# 4_ADC_DECOUPLING.net
KiCad netlist of a schematic drawn in Altium Designer
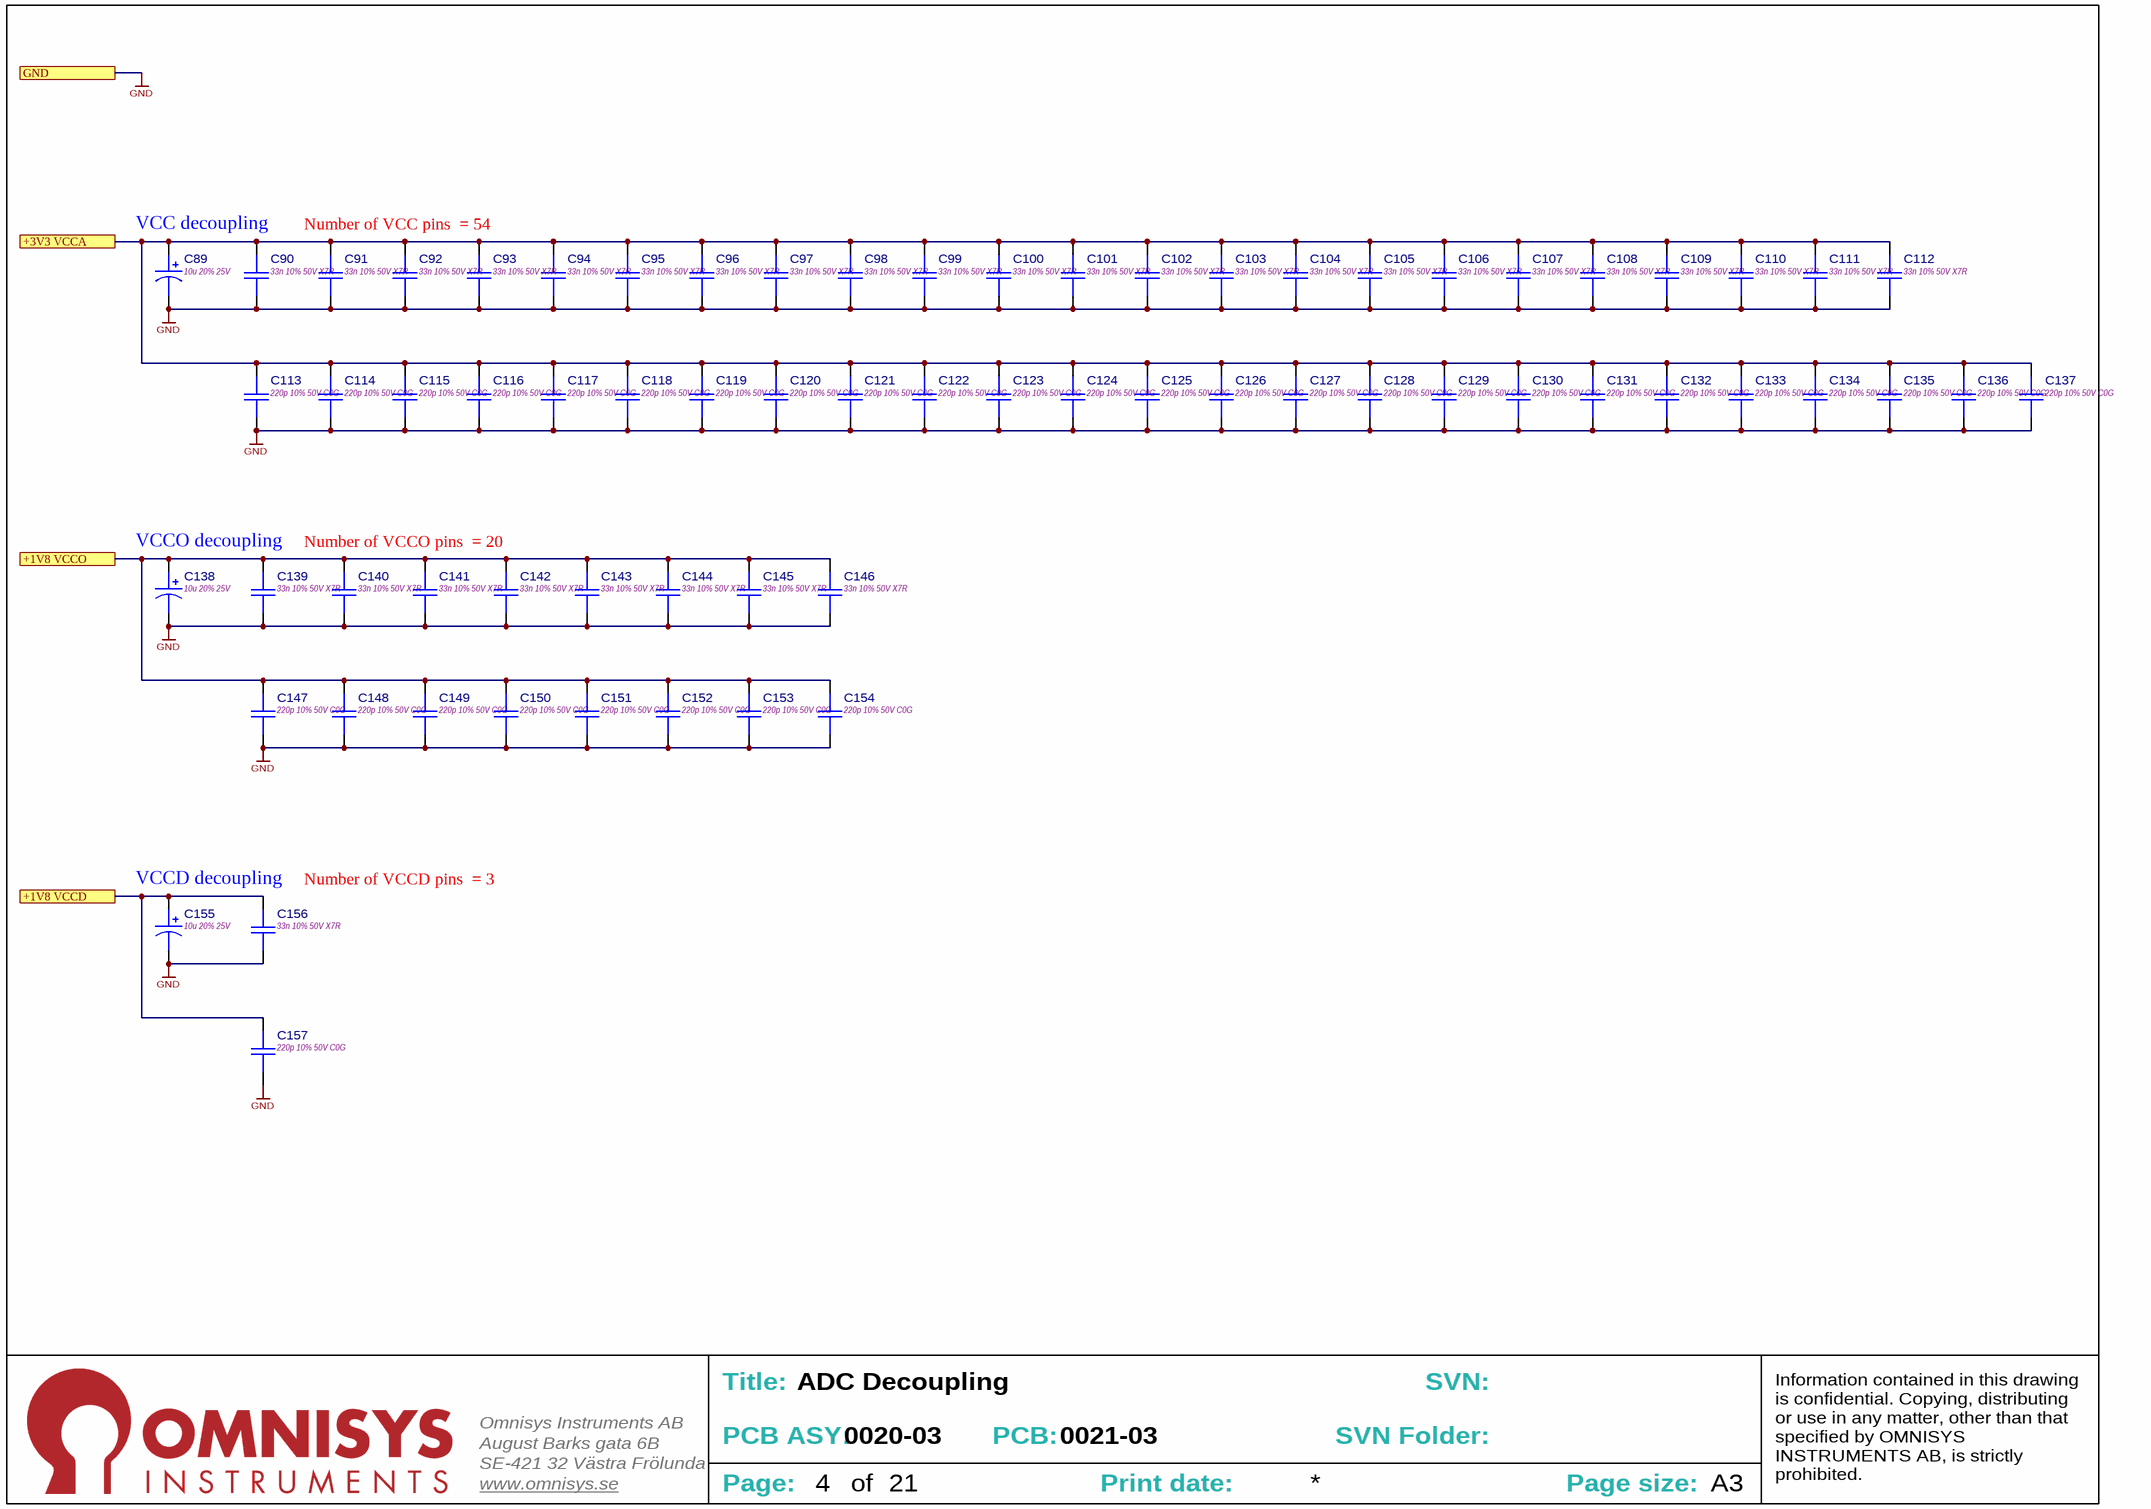
[diagram p0: [4] ADC_DECOUPLING.SchDoc]

(export (version "E")
  (design (tool "Eeschema 10.0.6"))
  (components
    (comp (ref "C89")
      (value "10u 20% 25V")
      (footprint "CAPMP3528X21N")
      (description "Standard tantalum capacitor, 3528/Case B")
      (fields (field (name "TOLERANCE") "20%"))
      (libsource (lib "Omnisys Vault") (part "CAP-2PIN-POL"))
    )
    (comp (ref "C90")
      (value "33n 10% 50V X7R")
      (footprint "CAPC1005X55L")
      (description "Ceramic Chip Capacitor, 0402/1005")
      (fields (field (name "TOLERANCE") "10%"))
      (libsource (lib "Omnisys Vault") (part "CAP-2PIN"))
    )
    (comp (ref "C91")
      (value "33n 10% 50V X7R")
      (footprint "CAPC1005X55L")
      (description "Ceramic Chip Capacitor, 0402/1005")
      (fields (field (name "TOLERANCE") "10%"))
      (libsource (lib "Omnisys Vault") (part "CAP-2PIN"))
    )
    (comp (ref "C92")
      (value "33n 10% 50V X7R")
      (footprint "CAPC1005X55L")
      (description "Ceramic Chip Capacitor, 0402/1005")
      (fields (field (name "TOLERANCE") "10%"))
      (libsource (lib "Omnisys Vault") (part "CAP-2PIN"))
    )
    (comp (ref "C93")
      (value "33n 10% 50V X7R")
      (footprint "CAPC1005X55L")
      (description "Ceramic Chip Capacitor, 0402/1005")
      (fields (field (name "TOLERANCE") "10%"))
      (libsource (lib "Omnisys Vault") (part "CAP-2PIN"))
    )
    (comp (ref "C94")
      (value "33n 10% 50V X7R")
      (footprint "CAPC1005X55L")
      (description "Ceramic Chip Capacitor, 0402/1005")
      (fields (field (name "TOLERANCE") "10%"))
      (libsource (lib "Omnisys Vault") (part "CAP-2PIN"))
    )
    (comp (ref "C95")
      (value "33n 10% 50V X7R")
      (footprint "CAPC1005X55L")
      (description "Ceramic Chip Capacitor, 0402/1005")
      (fields (field (name "TOLERANCE") "10%"))
      (libsource (lib "Omnisys Vault") (part "CAP-2PIN"))
    )
    (comp (ref "C96")
      (value "33n 10% 50V X7R")
      (footprint "CAPC1005X55L")
      (description "Ceramic Chip Capacitor, 0402/1005")
      (fields (field (name "TOLERANCE") "10%"))
      (libsource (lib "Omnisys Vault") (part "CAP-2PIN"))
    )
    (comp (ref "C97")
      (value "33n 10% 50V X7R")
      (footprint "CAPC1005X55L")
      (description "Ceramic Chip Capacitor, 0402/1005")
      (fields (field (name "TOLERANCE") "10%"))
      (libsource (lib "Omnisys Vault") (part "CAP-2PIN"))
    )
    (comp (ref "C98")
      (value "33n 10% 50V X7R")
      (footprint "CAPC1005X55L")
      (description "Ceramic Chip Capacitor, 0402/1005")
      (fields (field (name "TOLERANCE") "10%"))
      (libsource (lib "Omnisys Vault") (part "CAP-2PIN"))
    )
    (comp (ref "C99")
      (value "33n 10% 50V X7R")
      (footprint "CAPC1005X55L")
      (description "Ceramic Chip Capacitor, 0402/1005")
      (fields (field (name "TOLERANCE") "10%"))
      (libsource (lib "Omnisys Vault") (part "CAP-2PIN"))
    )
    (comp (ref "C100")
      (value "33n 10% 50V X7R")
      (footprint "CAPC1005X55L")
      (description "Ceramic Chip Capacitor, 0402/1005")
      (fields (field (name "TOLERANCE") "10%"))
      (libsource (lib "Omnisys Vault") (part "CAP-2PIN"))
    )
    (comp (ref "C101")
      (value "33n 10% 50V X7R")
      (footprint "CAPC1005X55L")
      (description "Ceramic Chip Capacitor, 0402/1005")
      (fields (field (name "TOLERANCE") "10%"))
      (libsource (lib "Omnisys Vault") (part "CAP-2PIN"))
    )
    (comp (ref "C102")
      (value "33n 10% 50V X7R")
      (footprint "CAPC1005X55L")
      (description "Ceramic Chip Capacitor, 0402/1005")
      (fields (field (name "TOLERANCE") "10%"))
      (libsource (lib "Omnisys Vault") (part "CAP-2PIN"))
    )
    (comp (ref "C103")
      (value "33n 10% 50V X7R")
      (footprint "CAPC1005X55L")
      (description "Ceramic Chip Capacitor, 0402/1005")
      (fields (field (name "TOLERANCE") "10%"))
      (libsource (lib "Omnisys Vault") (part "CAP-2PIN"))
    )
    (comp (ref "C104")
      (value "33n 10% 50V X7R")
      (footprint "CAPC1005X55L")
      (description "Ceramic Chip Capacitor, 0402/1005")
      (fields (field (name "TOLERANCE") "10%"))
      (libsource (lib "Omnisys Vault") (part "CAP-2PIN"))
    )
    (comp (ref "C105")
      (value "33n 10% 50V X7R")
      (footprint "CAPC1005X55L")
      (description "Ceramic Chip Capacitor, 0402/1005")
      (fields (field (name "TOLERANCE") "10%"))
      (libsource (lib "Omnisys Vault") (part "CAP-2PIN"))
    )
    (comp (ref "C106")
      (value "33n 10% 50V X7R")
      (footprint "CAPC1005X55L")
      (description "Ceramic Chip Capacitor, 0402/1005")
      (fields (field (name "TOLERANCE") "10%"))
      (libsource (lib "Omnisys Vault") (part "CAP-2PIN"))
    )
    (comp (ref "C107")
      (value "33n 10% 50V X7R")
      (footprint "CAPC1005X55L")
      (description "Ceramic Chip Capacitor, 0402/1005")
      (fields (field (name "TOLERANCE") "10%"))
      (libsource (lib "Omnisys Vault") (part "CAP-2PIN"))
    )
    (comp (ref "C108")
      (value "33n 10% 50V X7R")
      (footprint "CAPC1005X55L")
      (description "Ceramic Chip Capacitor, 0402/1005")
      (fields (field (name "TOLERANCE") "10%"))
      (libsource (lib "Omnisys Vault") (part "CAP-2PIN"))
    )
    (comp (ref "C109")
      (value "33n 10% 50V X7R")
      (footprint "CAPC1005X55L")
      (description "Ceramic Chip Capacitor, 0402/1005")
      (fields (field (name "TOLERANCE") "10%"))
      (libsource (lib "Omnisys Vault") (part "CAP-2PIN"))
    )
    (comp (ref "C110")
      (value "33n 10% 50V X7R")
      (footprint "CAPC1005X55L")
      (description "Ceramic Chip Capacitor, 0402/1005")
      (fields (field (name "TOLERANCE") "10%"))
      (libsource (lib "Omnisys Vault") (part "CAP-2PIN"))
    )
    (comp (ref "C111")
      (value "33n 10% 50V X7R")
      (footprint "CAPC1005X55L")
      (description "Ceramic Chip Capacitor, 0402/1005")
      (fields (field (name "TOLERANCE") "10%"))
      (libsource (lib "Omnisys Vault") (part "CAP-2PIN"))
    )
    (comp (ref "C112")
      (value "33n 10% 50V X7R")
      (footprint "CAPC1005X55L")
      (description "Ceramic Chip Capacitor, 0402/1005")
      (fields (field (name "TOLERANCE") "10%"))
      (libsource (lib "Omnisys Vault") (part "CAP-2PIN"))
    )
    (comp (ref "C113")
      (value "220p 10% 50V C0G")
      (footprint "CAPC1005X55L")
      (description "Ceramic Chip Capacitor, 0402/1005")
      (fields (field (name "TOLERANCE") "10%"))
      (libsource (lib "Omnisys Vault") (part "CAP-2PIN"))
    )
    (comp (ref "C114")
      (value "220p 10% 50V C0G")
      (footprint "CAPC1005X55L")
      (description "Ceramic Chip Capacitor, 0402/1005")
      (fields (field (name "TOLERANCE") "10%"))
      (libsource (lib "Omnisys Vault") (part "CAP-2PIN"))
    )
    (comp (ref "C115")
      (value "220p 10% 50V C0G")
      (footprint "CAPC1005X55L")
      (description "Ceramic Chip Capacitor, 0402/1005")
      (fields (field (name "TOLERANCE") "10%"))
      (libsource (lib "Omnisys Vault") (part "CAP-2PIN"))
    )
    (comp (ref "C116")
      (value "220p 10% 50V C0G")
      (footprint "CAPC1005X55L")
      (description "Ceramic Chip Capacitor, 0402/1005")
      (fields (field (name "TOLERANCE") "10%"))
      (libsource (lib "Omnisys Vault") (part "CAP-2PIN"))
    )
    (comp (ref "C117")
      (value "220p 10% 50V C0G")
      (footprint "CAPC1005X55L")
      (description "Ceramic Chip Capacitor, 0402/1005")
      (fields (field (name "TOLERANCE") "10%"))
      (libsource (lib "Omnisys Vault") (part "CAP-2PIN"))
    )
    (comp (ref "C118")
      (value "220p 10% 50V C0G")
      (footprint "CAPC1005X55L")
      (description "Ceramic Chip Capacitor, 0402/1005")
      (fields (field (name "TOLERANCE") "10%"))
      (libsource (lib "Omnisys Vault") (part "CAP-2PIN"))
    )
    (comp (ref "C119")
      (value "220p 10% 50V C0G")
      (footprint "CAPC1005X55L")
      (description "Ceramic Chip Capacitor, 0402/1005")
      (fields (field (name "TOLERANCE") "10%"))
      (libsource (lib "Omnisys Vault") (part "CAP-2PIN"))
    )
    (comp (ref "C120")
      (value "220p 10% 50V C0G")
      (footprint "CAPC1005X55L")
      (description "Ceramic Chip Capacitor, 0402/1005")
      (fields (field (name "TOLERANCE") "10%"))
      (libsource (lib "Omnisys Vault") (part "CAP-2PIN"))
    )
    (comp (ref "C121")
      (value "220p 10% 50V C0G")
      (footprint "CAPC1005X55L")
      (description "Ceramic Chip Capacitor, 0402/1005")
      (fields (field (name "TOLERANCE") "10%"))
      (libsource (lib "Omnisys Vault") (part "CAP-2PIN"))
    )
    (comp (ref "C122")
      (value "220p 10% 50V C0G")
      (footprint "CAPC1005X55L")
      (description "Ceramic Chip Capacitor, 0402/1005")
      (fields (field (name "TOLERANCE") "10%"))
      (libsource (lib "Omnisys Vault") (part "CAP-2PIN"))
    )
    (comp (ref "C123")
      (value "220p 10% 50V C0G")
      (footprint "CAPC1005X55L")
      (description "Ceramic Chip Capacitor, 0402/1005")
      (fields (field (name "TOLERANCE") "10%"))
      (libsource (lib "Omnisys Vault") (part "CAP-2PIN"))
    )
    (comp (ref "C124")
      (value "220p 10% 50V C0G")
      (footprint "CAPC1005X55L")
      (description "Ceramic Chip Capacitor, 0402/1005")
      (fields (field (name "TOLERANCE") "10%"))
      (libsource (lib "Omnisys Vault") (part "CAP-2PIN"))
    )
    (comp (ref "C125")
      (value "220p 10% 50V C0G")
      (footprint "CAPC1005X55L")
      (description "Ceramic Chip Capacitor, 0402/1005")
      (fields (field (name "TOLERANCE") "10%"))
      (libsource (lib "Omnisys Vault") (part "CAP-2PIN"))
    )
    (comp (ref "C126")
      (value "220p 10% 50V C0G")
      (footprint "CAPC1005X55L")
      (description "Ceramic Chip Capacitor, 0402/1005")
      (fields (field (name "TOLERANCE") "10%"))
      (libsource (lib "Omnisys Vault") (part "CAP-2PIN"))
    )
    (comp (ref "C127")
      (value "220p 10% 50V C0G")
      (footprint "CAPC1005X55L")
      (description "Ceramic Chip Capacitor, 0402/1005")
      (fields (field (name "TOLERANCE") "10%"))
      (libsource (lib "Omnisys Vault") (part "CAP-2PIN"))
    )
    (comp (ref "C128")
      (value "220p 10% 50V C0G")
      (footprint "CAPC1005X55L")
      (description "Ceramic Chip Capacitor, 0402/1005")
      (fields (field (name "TOLERANCE") "10%"))
      (libsource (lib "Omnisys Vault") (part "CAP-2PIN"))
    )
    (comp (ref "C129")
      (value "220p 10% 50V C0G")
      (footprint "CAPC1005X55L")
      (description "Ceramic Chip Capacitor, 0402/1005")
      (fields (field (name "TOLERANCE") "10%"))
      (libsource (lib "Omnisys Vault") (part "CAP-2PIN"))
    )
    (comp (ref "C130")
      (value "220p 10% 50V C0G")
      (footprint "CAPC1005X55L")
      (description "Ceramic Chip Capacitor, 0402/1005")
      (fields (field (name "TOLERANCE") "10%"))
      (libsource (lib "Omnisys Vault") (part "CAP-2PIN"))
    )
    (comp (ref "C131")
      (value "220p 10% 50V C0G")
      (footprint "CAPC1005X55L")
      (description "Ceramic Chip Capacitor, 0402/1005")
      (fields (field (name "TOLERANCE") "10%"))
      (libsource (lib "Omnisys Vault") (part "CAP-2PIN"))
    )
    (comp (ref "C132")
      (value "220p 10% 50V C0G")
      (footprint "CAPC1005X55L")
      (description "Ceramic Chip Capacitor, 0402/1005")
      (fields (field (name "TOLERANCE") "10%"))
      (libsource (lib "Omnisys Vault") (part "CAP-2PIN"))
    )
    (comp (ref "C133")
      (value "220p 10% 50V C0G")
      (footprint "CAPC1005X55L")
      (description "Ceramic Chip Capacitor, 0402/1005")
      (fields (field (name "TOLERANCE") "10%"))
      (libsource (lib "Omnisys Vault") (part "CAP-2PIN"))
    )
    (comp (ref "C134")
      (value "220p 10% 50V C0G")
      (footprint "CAPC1005X55L")
      (description "Ceramic Chip Capacitor, 0402/1005")
      (fields (field (name "TOLERANCE") "10%"))
      (libsource (lib "Omnisys Vault") (part "CAP-2PIN"))
    )
    (comp (ref "C135")
      (value "220p 10% 50V C0G")
      (footprint "CAPC1005X55L")
      (description "Ceramic Chip Capacitor, 0402/1005")
      (fields (field (name "TOLERANCE") "10%"))
      (libsource (lib "Omnisys Vault") (part "CAP-2PIN"))
    )
    (comp (ref "C136")
      (value "220p 10% 50V C0G")
      (footprint "CAPC1005X55L")
      (description "Ceramic Chip Capacitor, 0402/1005")
      (fields (field (name "TOLERANCE") "10%"))
      (libsource (lib "Omnisys Vault") (part "CAP-2PIN"))
    )
    (comp (ref "C137")
      (value "220p 10% 50V C0G")
      (footprint "CAPC1005X55L")
      (description "Ceramic Chip Capacitor, 0402/1005")
      (fields (field (name "TOLERANCE") "10%"))
      (libsource (lib "Omnisys Vault") (part "CAP-2PIN"))
    )
    (comp (ref "C138")
      (value "10u 20% 25V")
      (footprint "CAPMP3528X21N")
      (description "Standard tantalum capacitor, 3528/Case B")
      (fields (field (name "TOLERANCE") "20%"))
      (libsource (lib "Omnisys Vault") (part "CAP-2PIN-POL"))
    )
    (comp (ref "C139")
      (value "33n 10% 50V X7R")
      (footprint "CAPC1005X55N")
      (description "Ceramic Chip Capacitor, 0402/1005")
      (fields (field (name "TOLERANCE") "10%"))
      (libsource (lib "Omnisys Vault") (part "CAP-2PIN"))
    )
    (comp (ref "C140")
      (value "33n 10% 50V X7R")
      (footprint "CAPC1005X55N")
      (description "Ceramic Chip Capacitor, 0402/1005")
      (fields (field (name "TOLERANCE") "10%"))
      (libsource (lib "Omnisys Vault") (part "CAP-2PIN"))
    )
    (comp (ref "C141")
      (value "33n 10% 50V X7R")
      (footprint "CAPC1005X55N")
      (description "Ceramic Chip Capacitor, 0402/1005")
      (fields (field (name "TOLERANCE") "10%"))
      (libsource (lib "Omnisys Vault") (part "CAP-2PIN"))
    )
    (comp (ref "C142")
      (value "33n 10% 50V X7R")
      (footprint "CAPC1005X55N")
      (description "Ceramic Chip Capacitor, 0402/1005")
      (fields (field (name "TOLERANCE") "10%"))
      (libsource (lib "Omnisys Vault") (part "CAP-2PIN"))
    )
    (comp (ref "C143")
      (value "33n 10% 50V X7R")
      (footprint "CAPC1005X55N")
      (description "Ceramic Chip Capacitor, 0402/1005")
      (fields (field (name "TOLERANCE") "10%"))
      (libsource (lib "Omnisys Vault") (part "CAP-2PIN"))
    )
    (comp (ref "C144")
      (value "33n 10% 50V X7R")
      (footprint "CAPC1005X55N")
      (description "Ceramic Chip Capacitor, 0402/1005")
      (fields (field (name "TOLERANCE") "10%"))
      (libsource (lib "Omnisys Vault") (part "CAP-2PIN"))
    )
    (comp (ref "C145")
      (value "33n 10% 50V X7R")
      (footprint "CAPC1005X55N")
      (description "Ceramic Chip Capacitor, 0402/1005")
      (fields (field (name "TOLERANCE") "10%"))
      (libsource (lib "Omnisys Vault") (part "CAP-2PIN"))
    )
    (comp (ref "C146")
      (value "33n 10% 50V X7R")
      (footprint "CAPC1005X55N")
      (description "Ceramic Chip Capacitor, 0402/1005")
      (fields (field (name "TOLERANCE") "10%"))
      (libsource (lib "Omnisys Vault") (part "CAP-2PIN"))
    )
    (comp (ref "C147")
      (value "220p 10% 50V C0G")
      (footprint "CAPC1005X55N")
      (description "Ceramic Chip Capacitor, 0402/1005")
      (fields (field (name "TOLERANCE") "10%"))
      (libsource (lib "Omnisys Vault") (part "CAP-2PIN"))
    )
    (comp (ref "C148")
      (value "220p 10% 50V C0G")
      (footprint "CAPC1005X55N")
      (description "Ceramic Chip Capacitor, 0402/1005")
      (fields (field (name "TOLERANCE") "10%"))
      (libsource (lib "Omnisys Vault") (part "CAP-2PIN"))
    )
    (comp (ref "C149")
      (value "220p 10% 50V C0G")
      (footprint "CAPC1005X55N")
      (description "Ceramic Chip Capacitor, 0402/1005")
      (fields (field (name "TOLERANCE") "10%"))
      (libsource (lib "Omnisys Vault") (part "CAP-2PIN"))
    )
    (comp (ref "C150")
      (value "220p 10% 50V C0G")
      (footprint "CAPC1005X55N")
      (description "Ceramic Chip Capacitor, 0402/1005")
      (fields (field (name "TOLERANCE") "10%"))
      (libsource (lib "Omnisys Vault") (part "CAP-2PIN"))
    )
    (comp (ref "C151")
      (value "220p 10% 50V C0G")
      (footprint "CAPC1005X55N")
      (description "Ceramic Chip Capacitor, 0402/1005")
      (fields (field (name "TOLERANCE") "10%"))
      (libsource (lib "Omnisys Vault") (part "CAP-2PIN"))
    )
    (comp (ref "C152")
      (value "220p 10% 50V C0G")
      (footprint "CAPC1005X55N")
      (description "Ceramic Chip Capacitor, 0402/1005")
      (fields (field (name "TOLERANCE") "10%"))
      (libsource (lib "Omnisys Vault") (part "CAP-2PIN"))
    )
    (comp (ref "C153")
      (value "220p 10% 50V C0G")
      (footprint "CAPC1005X55N")
      (description "Ceramic Chip Capacitor, 0402/1005")
      (fields (field (name "TOLERANCE") "10%"))
      (libsource (lib "Omnisys Vault") (part "CAP-2PIN"))
    )
    (comp (ref "C154")
      (value "220p 10% 50V C0G")
      (footprint "CAPC1005X55N")
      (description "Ceramic Chip Capacitor, 0402/1005")
      (fields (field (name "TOLERANCE") "10%"))
      (libsource (lib "Omnisys Vault") (part "CAP-2PIN"))
    )
    (comp (ref "C155")
      (value "10u 20% 25V")
      (footprint "CAPMP3528X21N")
      (description "Standard tantalum capacitor, 3528/Case B")
      (fields (field (name "TOLERANCE") "20%"))
      (libsource (lib "Omnisys Vault") (part "CAP-2PIN-POL"))
    )
    (comp (ref "C156")
      (value "33n 10% 50V X7R")
      (footprint "CAPC1005X55N")
      (description "Ceramic Chip Capacitor, 0402/1005")
      (fields (field (name "TOLERANCE") "10%"))
      (libsource (lib "Omnisys Vault") (part "CAP-2PIN"))
    )
    (comp (ref "C157")
      (value "220p 10% 50V C0G")
      (footprint "CAPC1005X55N")
      (description "Ceramic Chip Capacitor, 0402/1005")
      (fields (field (name "TOLERANCE") "10%"))
      (libsource (lib "Omnisys Vault") (part "CAP-2PIN"))
    )
  )
  (nets
    (net (code "1") (name "/+1V8 VCCD") (class "Default")
      (node (ref "C155") (pin "1") (pinfunction "1_1") (pintype "passive"))
      (node (ref "C156") (pin "2") (pinfunction "2_2") (pintype "passive"))
      (node (ref "C157") (pin "2") (pinfunction "2_2") (pintype "passive"))
    )
    (net (code "2") (name "/+1V8 VCCO") (class "Default")
      (node (ref "C138") (pin "1") (pinfunction "1_1") (pintype "passive"))
      (node (ref "C139") (pin "2") (pinfunction "2_2") (pintype "passive"))
      (node (ref "C140") (pin "2") (pinfunction "2_2") (pintype "passive"))
      (node (ref "C141") (pin "2") (pinfunction "2_2") (pintype "passive"))
      (node (ref "C142") (pin "2") (pinfunction "2_2") (pintype "passive"))
      (node (ref "C143") (pin "2") (pinfunction "2_2") (pintype "passive"))
      (node (ref "C144") (pin "2") (pinfunction "2_2") (pintype "passive"))
      (node (ref "C145") (pin "2") (pinfunction "2_2") (pintype "passive"))
      (node (ref "C146") (pin "2") (pinfunction "2_2") (pintype "passive"))
      (node (ref "C147") (pin "2") (pinfunction "2_2") (pintype "passive"))
      (node (ref "C148") (pin "2") (pinfunction "2_2") (pintype "passive"))
      (node (ref "C149") (pin "2") (pinfunction "2_2") (pintype "passive"))
      (node (ref "C150") (pin "2") (pinfunction "2_2") (pintype "passive"))
      (node (ref "C151") (pin "2") (pinfunction "2_2") (pintype "passive"))
      (node (ref "C152") (pin "2") (pinfunction "2_2") (pintype "passive"))
      (node (ref "C153") (pin "2") (pinfunction "2_2") (pintype "passive"))
      (node (ref "C154") (pin "2") (pinfunction "2_2") (pintype "passive"))
    )
    (net (code "3") (name "/+3V3 VCCA") (class "Default")
      (node (ref "C100") (pin "2") (pinfunction "2_2") (pintype "passive"))
      (node (ref "C101") (pin "2") (pinfunction "2_2") (pintype "passive"))
      (node (ref "C102") (pin "2") (pinfunction "2_2") (pintype "passive"))
      (node (ref "C103") (pin "2") (pinfunction "2_2") (pintype "passive"))
      (node (ref "C104") (pin "2") (pinfunction "2_2") (pintype "passive"))
      (node (ref "C105") (pin "2") (pinfunction "2_2") (pintype "passive"))
      (node (ref "C106") (pin "2") (pinfunction "2_2") (pintype "passive"))
      (node (ref "C107") (pin "2") (pinfunction "2_2") (pintype "passive"))
      (node (ref "C108") (pin "2") (pinfunction "2_2") (pintype "passive"))
      (node (ref "C109") (pin "2") (pinfunction "2_2") (pintype "passive"))
      (node (ref "C110") (pin "2") (pinfunction "2_2") (pintype "passive"))
      (node (ref "C111") (pin "2") (pinfunction "2_2") (pintype "passive"))
      (node (ref "C112") (pin "2") (pinfunction "2_2") (pintype "passive"))
      (node (ref "C113") (pin "2") (pinfunction "2_2") (pintype "passive"))
      (node (ref "C114") (pin "2") (pinfunction "2_2") (pintype "passive"))
      (node (ref "C115") (pin "2") (pinfunction "2_2") (pintype "passive"))
      (node (ref "C116") (pin "2") (pinfunction "2_2") (pintype "passive"))
      (node (ref "C117") (pin "2") (pinfunction "2_2") (pintype "passive"))
      (node (ref "C118") (pin "2") (pinfunction "2_2") (pintype "passive"))
      (node (ref "C119") (pin "2") (pinfunction "2_2") (pintype "passive"))
      (node (ref "C120") (pin "2") (pinfunction "2_2") (pintype "passive"))
      (node (ref "C121") (pin "2") (pinfunction "2_2") (pintype "passive"))
      (node (ref "C122") (pin "2") (pinfunction "2_2") (pintype "passive"))
      (node (ref "C123") (pin "2") (pinfunction "2_2") (pintype "passive"))
      (node (ref "C124") (pin "2") (pinfunction "2_2") (pintype "passive"))
      (node (ref "C125") (pin "2") (pinfunction "2_2") (pintype "passive"))
      (node (ref "C126") (pin "2") (pinfunction "2_2") (pintype "passive"))
      (node (ref "C127") (pin "2") (pinfunction "2_2") (pintype "passive"))
      (node (ref "C128") (pin "2") (pinfunction "2_2") (pintype "passive"))
      (node (ref "C129") (pin "2") (pinfunction "2_2") (pintype "passive"))
      (node (ref "C130") (pin "2") (pinfunction "2_2") (pintype "passive"))
      (node (ref "C131") (pin "2") (pinfunction "2_2") (pintype "passive"))
      (node (ref "C132") (pin "2") (pinfunction "2_2") (pintype "passive"))
      (node (ref "C133") (pin "2") (pinfunction "2_2") (pintype "passive"))
      (node (ref "C134") (pin "2") (pinfunction "2_2") (pintype "passive"))
      (node (ref "C135") (pin "2") (pinfunction "2_2") (pintype "passive"))
      (node (ref "C136") (pin "2") (pinfunction "2_2") (pintype "passive"))
      (node (ref "C137") (pin "2") (pinfunction "2_2") (pintype "passive"))
      (node (ref "C89") (pin "1") (pinfunction "1_1") (pintype "passive"))
      (node (ref "C90") (pin "2") (pinfunction "2_2") (pintype "passive"))
      (node (ref "C91") (pin "2") (pinfunction "2_2") (pintype "passive"))
      (node (ref "C92") (pin "2") (pinfunction "2_2") (pintype "passive"))
      (node (ref "C93") (pin "2") (pinfunction "2_2") (pintype "passive"))
      (node (ref "C94") (pin "2") (pinfunction "2_2") (pintype "passive"))
      (node (ref "C95") (pin "2") (pinfunction "2_2") (pintype "passive"))
      (node (ref "C96") (pin "2") (pinfunction "2_2") (pintype "passive"))
      (node (ref "C97") (pin "2") (pinfunction "2_2") (pintype "passive"))
      (node (ref "C98") (pin "2") (pinfunction "2_2") (pintype "passive"))
      (node (ref "C99") (pin "2") (pinfunction "2_2") (pintype "passive"))
    )
    (net (code "4") (name "GND") (class "Default")
      (node (ref "C100") (pin "1") (pinfunction "1_1") (pintype "passive"))
      (node (ref "C101") (pin "1") (pinfunction "1_1") (pintype "passive"))
      (node (ref "C102") (pin "1") (pinfunction "1_1") (pintype "passive"))
      (node (ref "C103") (pin "1") (pinfunction "1_1") (pintype "passive"))
      (node (ref "C104") (pin "1") (pinfunction "1_1") (pintype "passive"))
      (node (ref "C105") (pin "1") (pinfunction "1_1") (pintype "passive"))
      (node (ref "C106") (pin "1") (pinfunction "1_1") (pintype "passive"))
      (node (ref "C107") (pin "1") (pinfunction "1_1") (pintype "passive"))
      (node (ref "C108") (pin "1") (pinfunction "1_1") (pintype "passive"))
      (node (ref "C109") (pin "1") (pinfunction "1_1") (pintype "passive"))
      (node (ref "C110") (pin "1") (pinfunction "1_1") (pintype "passive"))
      (node (ref "C111") (pin "1") (pinfunction "1_1") (pintype "passive"))
      (node (ref "C112") (pin "1") (pinfunction "1_1") (pintype "passive"))
      (node (ref "C113") (pin "1") (pinfunction "1_1") (pintype "passive"))
      (node (ref "C114") (pin "1") (pinfunction "1_1") (pintype "passive"))
      (node (ref "C115") (pin "1") (pinfunction "1_1") (pintype "passive"))
      (node (ref "C116") (pin "1") (pinfunction "1_1") (pintype "passive"))
      (node (ref "C117") (pin "1") (pinfunction "1_1") (pintype "passive"))
      (node (ref "C118") (pin "1") (pinfunction "1_1") (pintype "passive"))
      (node (ref "C119") (pin "1") (pinfunction "1_1") (pintype "passive"))
      (node (ref "C120") (pin "1") (pinfunction "1_1") (pintype "passive"))
      (node (ref "C121") (pin "1") (pinfunction "1_1") (pintype "passive"))
      (node (ref "C122") (pin "1") (pinfunction "1_1") (pintype "passive"))
      (node (ref "C123") (pin "1") (pinfunction "1_1") (pintype "passive"))
      (node (ref "C124") (pin "1") (pinfunction "1_1") (pintype "passive"))
      (node (ref "C125") (pin "1") (pinfunction "1_1") (pintype "passive"))
      (node (ref "C126") (pin "1") (pinfunction "1_1") (pintype "passive"))
      (node (ref "C127") (pin "1") (pinfunction "1_1") (pintype "passive"))
      (node (ref "C128") (pin "1") (pinfunction "1_1") (pintype "passive"))
      (node (ref "C129") (pin "1") (pinfunction "1_1") (pintype "passive"))
      (node (ref "C130") (pin "1") (pinfunction "1_1") (pintype "passive"))
      (node (ref "C131") (pin "1") (pinfunction "1_1") (pintype "passive"))
      (node (ref "C132") (pin "1") (pinfunction "1_1") (pintype "passive"))
      (node (ref "C133") (pin "1") (pinfunction "1_1") (pintype "passive"))
      (node (ref "C134") (pin "1") (pinfunction "1_1") (pintype "passive"))
      (node (ref "C135") (pin "1") (pinfunction "1_1") (pintype "passive"))
      (node (ref "C136") (pin "1") (pinfunction "1_1") (pintype "passive"))
      (node (ref "C137") (pin "1") (pinfunction "1_1") (pintype "passive"))
      (node (ref "C138") (pin "2") (pinfunction "2_2") (pintype "passive"))
      (node (ref "C139") (pin "1") (pinfunction "1_1") (pintype "passive"))
      (node (ref "C140") (pin "1") (pinfunction "1_1") (pintype "passive"))
      (node (ref "C141") (pin "1") (pinfunction "1_1") (pintype "passive"))
      (node (ref "C142") (pin "1") (pinfunction "1_1") (pintype "passive"))
      (node (ref "C143") (pin "1") (pinfunction "1_1") (pintype "passive"))
      (node (ref "C144") (pin "1") (pinfunction "1_1") (pintype "passive"))
      (node (ref "C145") (pin "1") (pinfunction "1_1") (pintype "passive"))
      (node (ref "C146") (pin "1") (pinfunction "1_1") (pintype "passive"))
      (node (ref "C147") (pin "1") (pinfunction "1_1") (pintype "passive"))
      (node (ref "C148") (pin "1") (pinfunction "1_1") (pintype "passive"))
      (node (ref "C149") (pin "1") (pinfunction "1_1") (pintype "passive"))
      (node (ref "C150") (pin "1") (pinfunction "1_1") (pintype "passive"))
      (node (ref "C151") (pin "1") (pinfunction "1_1") (pintype "passive"))
      (node (ref "C152") (pin "1") (pinfunction "1_1") (pintype "passive"))
      (node (ref "C153") (pin "1") (pinfunction "1_1") (pintype "passive"))
      (node (ref "C154") (pin "1") (pinfunction "1_1") (pintype "passive"))
      (node (ref "C155") (pin "2") (pinfunction "2_2") (pintype "passive"))
      (node (ref "C156") (pin "1") (pinfunction "1_1") (pintype "passive"))
      (node (ref "C157") (pin "1") (pinfunction "1_1") (pintype "passive"))
      (node (ref "C89") (pin "2") (pinfunction "2_2") (pintype "passive"))
      (node (ref "C90") (pin "1") (pinfunction "1_1") (pintype "passive"))
      (node (ref "C91") (pin "1") (pinfunction "1_1") (pintype "passive"))
      (node (ref "C92") (pin "1") (pinfunction "1_1") (pintype "passive"))
      (node (ref "C93") (pin "1") (pinfunction "1_1") (pintype "passive"))
      (node (ref "C94") (pin "1") (pinfunction "1_1") (pintype "passive"))
      (node (ref "C95") (pin "1") (pinfunction "1_1") (pintype "passive"))
      (node (ref "C96") (pin "1") (pinfunction "1_1") (pintype "passive"))
      (node (ref "C97") (pin "1") (pinfunction "1_1") (pintype "passive"))
      (node (ref "C98") (pin "1") (pinfunction "1_1") (pintype "passive"))
      (node (ref "C99") (pin "1") (pinfunction "1_1") (pintype "passive"))
    )
  )
)
